# SIM800L.net
KiCad netlist of a schematic drawn in EAGLE
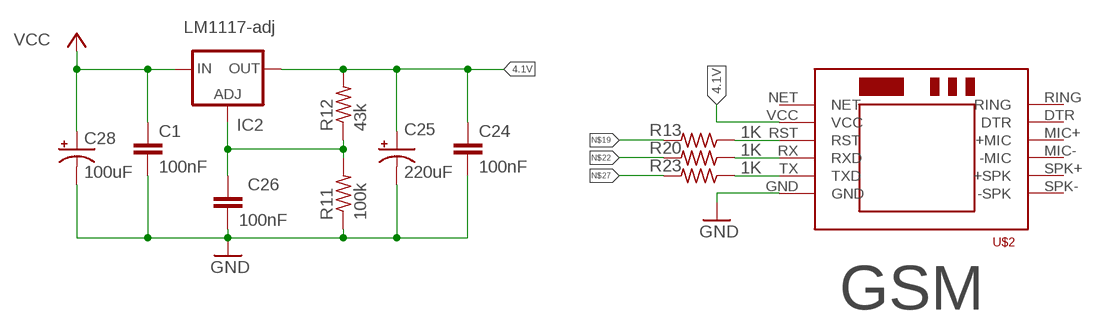
[diagram p0: schematic, sheet 1]

(export (version "E")
  (design (tool "Eeschema 10.0.6"))
  (components
    (comp (ref "C1")
      (value "100nF")
      (footprint "eagle-import:C050-024X044")
      (libsource (lib "eagle-import") (part "C-EU050-024X044"))
    )
    (comp (ref "C24")
      (value "100nF")
      (footprint "eagle-import:C050-024X044")
      (libsource (lib "eagle-import") (part "C-EU050-024X044"))
    )
    (comp (ref "C25")
      (value "220uF")
      (footprint "eagle-import:E2,5-6")
      (libsource (lib "eagle-import") (part "CPOL-USE2.5-6"))
    )
    (comp (ref "C26")
      (value "100nF")
      (footprint "eagle-import:C050-024X044")
      (libsource (lib "eagle-import") (part "C-EU050-024X044"))
    )
    (comp (ref "C28")
      (value "100uF")
      (footprint "eagle-import:E2,5-6")
      (libsource (lib "eagle-import") (part "CPOL-USE2.5-6"))
    )
    (comp (ref "IC2")
      (value "LM1117-adj")
      (footprint "eagle-import:SOT223")
      (libsource (lib "eagle-import") (part "LD117A?S25TR"))
    )
    (comp (ref "R11")
      (value "100k")
      (footprint "eagle-import:0204_7")
      (libsource (lib "eagle-import") (part "R-US_0204/7"))
    )
    (comp (ref "R12")
      (value "43k")
      (footprint "eagle-import:0204_7")
      (libsource (lib "eagle-import") (part "R-US_0204/7"))
    )
    (comp (ref "R13")
      (value "1K")
      (footprint "eagle-import:0204_7")
      (libsource (lib "eagle-import") (part "R-US_0204/7"))
    )
    (comp (ref "R20")
      (value "1K")
      (footprint "eagle-import:0204_7")
      (libsource (lib "eagle-import") (part "R-US_0204/7"))
    )
    (comp (ref "R23")
      (value "1K")
      (footprint "eagle-import:0204_7")
      (libsource (lib "eagle-import") (part "R-US_0204/7"))
    )
    (comp (ref "U$2")
      (value "SIM800LMODULE")
      (footprint "eagle-import:SIM800LMODULE")
      (libsource (lib "eagle-import") (part "SIM800LMODULE"))
    )
  )
  (nets
    (net (code "1") (name "4.1V") (class "Default")
      (node (ref "C24") (pin "1") (pinfunction "1_1") (pintype "passive"))
      (node (ref "C25") (pin "+") (pinfunction "+_+") (pintype "passive"))
      (node (ref "IC2") (pin "4") (pinfunction "OUT_4") (pintype "passive"))
      (node (ref "R12") (pin "2") (pinfunction "2_2") (pintype "passive"))
      (node (ref "U$2") (pin "VCC") (pinfunction "VCC_VCC") (pintype "bidirectional"))
    )
    (net (code "2") (name "GND") (class "Default")
      (node (ref "C1") (pin "2") (pinfunction "2_2") (pintype "passive"))
      (node (ref "C24") (pin "2") (pinfunction "2_2") (pintype "passive"))
      (node (ref "C25") (pin "-") (pinfunction "-_-") (pintype "passive"))
      (node (ref "C26") (pin "2") (pinfunction "2_2") (pintype "passive"))
      (node (ref "C28") (pin "-") (pinfunction "-_-") (pintype "passive"))
      (node (ref "R11") (pin "1") (pinfunction "1_1") (pintype "passive"))
      (node (ref "U$2") (pin "GND") (pinfunction "GND_GND") (pintype "bidirectional"))
    )
    (net (code "3") (name "N$19") (class "Default")
      (node (ref "R13") (pin "2") (pinfunction "2_2") (pintype "passive"))
    )
    (net (code "4") (name "N$22") (class "Default")
      (node (ref "R20") (pin "2") (pinfunction "2_2") (pintype "passive"))
    )
    (net (code "5") (name "N$27") (class "Default")
      (node (ref "R23") (pin "2") (pinfunction "2_2") (pintype "passive"))
    )
    (net (code "6") (name "Net-(IC2-ADJ)") (class "Default")
      (node (ref "C26") (pin "1") (pinfunction "1_1") (pintype "passive"))
      (node (ref "IC2") (pin "1") (pinfunction "ADJ_1") (pintype "input"))
      (node (ref "R11") (pin "2") (pinfunction "2_2") (pintype "passive"))
      (node (ref "R12") (pin "1") (pinfunction "1_1") (pintype "passive"))
    )
    (net (code "7") (name "Net-(R13-Pad1)") (class "Default")
      (node (ref "R13") (pin "1") (pinfunction "1_1") (pintype "passive"))
      (node (ref "U$2") (pin "RST") (pinfunction "RST_RST") (pintype "bidirectional"))
    )
    (net (code "8") (name "Net-(U$2-RXD)") (class "Default")
      (node (ref "R20") (pin "1") (pinfunction "1_1") (pintype "passive"))
      (node (ref "U$2") (pin "RX") (pinfunction "RXD_RX") (pintype "bidirectional"))
    )
    (net (code "9") (name "Net-(U$2-TXD)") (class "Default")
      (node (ref "R23") (pin "1") (pinfunction "1_1") (pintype "passive"))
      (node (ref "U$2") (pin "TX") (pinfunction "TXD_TX") (pintype "bidirectional"))
    )
    (net (code "10") (name "VCC") (class "Default")
      (node (ref "C1") (pin "1") (pinfunction "1_1") (pintype "passive"))
      (node (ref "C28") (pin "+") (pinfunction "+_+") (pintype "passive"))
      (node (ref "IC2") (pin "3") (pinfunction "IN_3") (pintype "input"))
    )
    (net (code "11") (name "unconnected-(U$2-+MIC-PadMIC+)") (class "Default")
      (node (ref "U$2") (pin "MIC+") (pinfunction "+MIC_MIC+") (pintype "bidirectional"))
    )
    (net (code "12") (name "unconnected-(U$2-+SPK-PadSPK+)") (class "Default")
      (node (ref "U$2") (pin "SPK+") (pinfunction "+SPK_SPK+") (pintype "bidirectional"))
    )
    (net (code "13") (name "unconnected-(U$2--MIC-PadMIC-)") (class "Default")
      (node (ref "U$2") (pin "MIC-") (pinfunction "-MIC_MIC-") (pintype "bidirectional"))
    )
    (net (code "14") (name "unconnected-(U$2--SPK-PadSPK-)") (class "Default")
      (node (ref "U$2") (pin "SPK-") (pinfunction "-SPK_SPK-") (pintype "bidirectional"))
    )
    (net (code "15") (name "unconnected-(U$2-PadDTR)") (class "Default")
      (node (ref "U$2") (pin "DTR") (pinfunction "DTR_DTR") (pintype "bidirectional"))
    )
    (net (code "16") (name "unconnected-(U$2-PadNET)") (class "Default")
      (node (ref "U$2") (pin "NET") (pinfunction "NET_NET") (pintype "bidirectional"))
    )
    (net (code "17") (name "unconnected-(U$2-PadRING)") (class "Default")
      (node (ref "U$2") (pin "RING") (pinfunction "RING_RING") (pintype "bidirectional"))
    )
  )
)
